# Last_project.net
KiCad netlist of a schematic drawn in Altium Designer
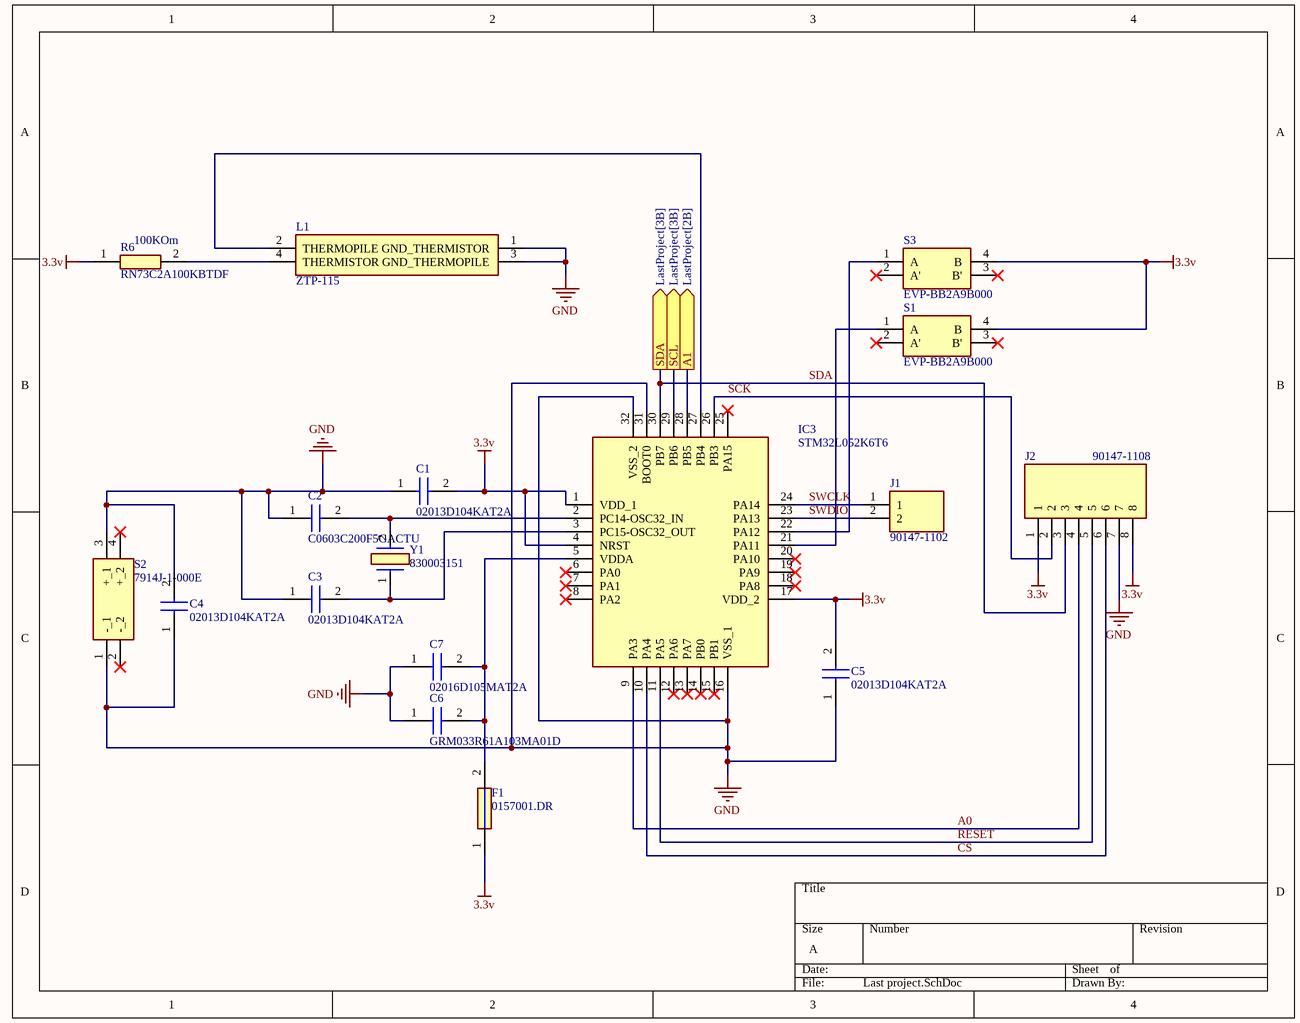
[diagram p0: Last project.SchDoc]

(export (version "E")
  (design (tool "Eeschema 10.0.6"))
  (components
    (comp (ref "C1")
      (value "02013D104KAT2A")
      (footprint "SamacSys:CAPC0603X33N")
      (description "Capacitor")
      (fields (field (name "MOUSER PART NUMBER") "581-02013D104KAT2A"))
      (libsource (lib "*") (part "02013D104KAT2A"))
    )
    (comp (ref "C2")
      (value "C0603C200F5GACTU")
      (footprint "SamacSys:CAPC1608X87N")
      (description "Capacitor")
      (fields (field (name "MOUSER PART NUMBER") "80-C0603C200F5GACTU"))
      (libsource (lib "*") (part "C0603C200F5GACTU"))
    )
    (comp (ref "C3")
      (value "02013D104KAT2A")
      (footprint "SamacSys:CAPC0603X33N")
      (description "Capacitor")
      (fields (field (name "MOUSER PART NUMBER") "581-02013D104KAT2A"))
      (libsource (lib "*") (part "02013D104KAT2A"))
    )
    (comp (ref "C4")
      (value "02013D104KAT2A")
      (footprint "SamacSys:CAPC0603X33N")
      (description "Capacitor")
      (fields (field (name "MOUSER PART NUMBER") "581-02013D104KAT2A"))
      (libsource (lib "*") (part "02013D104KAT2A"))
    )
    (comp (ref "C5")
      (value "02013D104KAT2A")
      (footprint "SamacSys:CAPC0603X33N")
      (description "Capacitor")
      (fields (field (name "MOUSER PART NUMBER") "581-02013D104KAT2A"))
      (libsource (lib "*") (part "02013D104KAT2A"))
    )
    (comp (ref "C6")
      (value "GRM033R61A103MA01D")
      (footprint "SamacSys:GRM033D70J224ME01D")
      (description "Capacitor")
      (fields (field (name "MOUSER PART NUMBER") "81-GRM033R61A103MA1D"))
      (libsource (lib "*") (part "GRM033R61A103MA01D"))
    )
    (comp (ref "C7")
      (value "02016D105MAT2A")
      (footprint "SamacSys:CAPC0603X33N")
      (description "Capacitor")
      (fields (field (name "MOUSER PART NUMBER") "581-02016D105MAT2A"))
      (libsource (lib "*") (part "02016D105MAT2A"))
    )
    (comp (ref "F1")
      (value "0157001.DR")
      (footprint "SamacSys:FUSC6537X403N")
      (description "Fuse")
      (fields (field (name "MOUSER PART NUMBER") "576-0157001.DR"))
      (libsource (lib "*") (part "0157001.DR"))
    )
    (comp (ref "IC3")
      (value "STM32L052K6T6")
      (footprint "SamacSys:QFP80P900X900X160-32N")
      (description "Integrated Circuit")
      (fields (field (name "MOUSER PART NUMBER") "511-STM32L052K6T6"))
      (libsource (lib "*") (part "STM32L052K6T6"))
    )
    (comp (ref "J1")
      (value "90147-1102")
      (footprint "SamacSys:RHDR2W70P0X254_1X2_493X244X870P")
      (description "Connector")
      (fields (field (name "MOUSER PART NUMBER") "538-90147-1102"))
      (libsource (lib "*") (part "90147-1102"))
    )
    (comp (ref "J2")
      (value "90147-1108")
      (footprint "SamacSys:RHDR8W70P0X254_1X8_2017X244X870P")
      (description "Connector")
      (fields (field (name "MOUSER PART NUMBER") "538-90147-1108"))
      (libsource (lib "*") (part "90147-1108"))
    )
    (comp (ref "L1")
      (value "ZTP-115")
      (footprint "SamacSys:ZTP115")
      (description "Inductor")
      (fields (field (name "MOUSER PART NUMBER") "527-ZTP-115-STD"))
      (libsource (lib "*") (part "ZTP-115"))
    )
    (comp (ref "R6")
      (value "RN73C2A100KBTDF")
      (footprint "SamacSys:RESC2012X65N")
      (description "Resistor")
      (fields (field (name "MOUSER PART NUMBER") "279-RN73CA-100K"))
      (libsource (lib "*") (part "RN73C2A100KBTDF"))
    )
    (comp (ref "S1")
      (value "EVP-BB2A9B000")
      (footprint "SamacSys:EVPBB2A9B000")
      (description "Switch")
      (fields (field (name "MOUSER PART NUMBER") "667-EVP-BB2A9B000"))
      (libsource (lib "*") (part "EVP-BB2A9B000"))
    )
    (comp (ref "S2")
      (value "7914J-1-000E")
      (footprint "SamacSys:7914J1000E")
      (description "Switch")
      (fields (field (name "MOUSER PART NUMBER") "652-7914J-1-000E"))
      (libsource (lib "*") (part "7914J-1-000E"))
    )
    (comp (ref "S3")
      (value "EVP-BB2A9B000")
      (footprint "SamacSys:EVPBB2A9B000")
      (description "Switch")
      (fields (field (name "MOUSER PART NUMBER") "667-EVP-BB2A9B000"))
      (libsource (lib "*") (part "EVP-BB2A9B000"))
    )
    (comp (ref "Y1")
      (value "830003151")
      (footprint "SamacSys:830003151")
      (description "Crystal or Oscillator")
      (fields (field (name "MOUSER PART NUMBER") "710-830003151"))
      (libsource (lib "*") (part "830003151"))
    )
  )
  (nets
    (net (code "1") (name "/A0") (class "Default")
      (node (ref "IC3") (pin "9") (pinfunction "PA3_9") (pintype "passive"))
      (node (ref "J2") (pin "4") (pinfunction "4_4") (pintype "passive"))
    )
    (net (code "2") (name "/A1") (class "Default")
      (node (ref "IC3") (pin "28") (pinfunction "PB5_28") (pintype "passive"))
    )
    (net (code "3") (name "/CS") (class "Default")
      (node (ref "IC3") (pin "10") (pinfunction "PA4_10") (pintype "passive"))
      (node (ref "J2") (pin "6") (pinfunction "6_6") (pintype "passive"))
    )
    (net (code "4") (name "/RESET") (class "Default")
      (node (ref "IC3") (pin "11") (pinfunction "PA5_11") (pintype "passive"))
      (node (ref "J2") (pin "5") (pinfunction "5_5") (pintype "passive"))
    )
    (net (code "5") (name "/SCK") (class "Default")
      (node (ref "IC3") (pin "26") (pinfunction "PB3_26") (pintype "passive"))
      (node (ref "J2") (pin "2") (pinfunction "2_2") (pintype "passive"))
    )
    (net (code "6") (name "/SCL") (class "Default")
      (node (ref "IC3") (pin "29") (pinfunction "PB6_29") (pintype "passive"))
    )
    (net (code "7") (name "/SDA") (class "Default")
      (node (ref "IC3") (pin "30") (pinfunction "PB7_30") (pintype "passive"))
      (node (ref "J2") (pin "3") (pinfunction "3_3") (pintype "passive"))
    )
    (net (code "8") (name "/SWCLK") (class "Default")
      (node (ref "IC3") (pin "24") (pinfunction "PA14_24") (pintype "passive"))
      (node (ref "J1") (pin "1") (pinfunction "1_1") (pintype "passive"))
    )
    (net (code "9") (name "/SWDIO") (class "Default")
      (node (ref "IC3") (pin "23") (pinfunction "PA13_23") (pintype "passive"))
      (node (ref "J1") (pin "2") (pinfunction "2_2") (pintype "passive"))
    )
    (net (code "10") (name "3.3v") (class "Default")
      (node (ref "C1") (pin "2") (pinfunction "2_2") (pintype "passive"))
      (node (ref "C5") (pin "2") (pinfunction "2_2") (pintype "passive"))
      (node (ref "F1") (pin "1") (pinfunction "1_1") (pintype "passive"))
      (node (ref "IC3") (pin "1") (pinfunction "VDD_1_1") (pintype "passive"))
      (node (ref "IC3") (pin "17") (pinfunction "VDD_2_17") (pintype "passive"))
      (node (ref "IC3") (pin "4") (pinfunction "NRST_4") (pintype "passive"))
      (node (ref "J2") (pin "1") (pinfunction "1_1") (pintype "passive"))
      (node (ref "J2") (pin "8") (pinfunction "8_8") (pintype "passive"))
      (node (ref "R6") (pin "1") (pinfunction "1_1") (pintype "passive"))
      (node (ref "S1") (pin "4") (pinfunction "B_4") (pintype "passive"))
      (node (ref "S3") (pin "4") (pinfunction "B_4") (pintype "passive"))
    )
    (net (code "11") (name "GND") (class "Default")
      (node (ref "C1") (pin "1") (pinfunction "1_1") (pintype "passive"))
      (node (ref "C2") (pin "1") (pinfunction "1_1") (pintype "passive"))
      (node (ref "C3") (pin "1") (pinfunction "1_1") (pintype "passive"))
      (node (ref "C4") (pin "1") (pinfunction "1_1") (pintype "passive"))
      (node (ref "C4") (pin "2") (pinfunction "2_2") (pintype "passive"))
      (node (ref "C5") (pin "1") (pinfunction "1_1") (pintype "passive"))
      (node (ref "C6") (pin "1") (pinfunction "1_1") (pintype "passive"))
      (node (ref "C7") (pin "1") (pinfunction "1_1") (pintype "passive"))
      (node (ref "IC3") (pin "16") (pinfunction "VSS_1_16") (pintype "passive"))
      (node (ref "IC3") (pin "31") (pinfunction "BOOT0_31") (pintype "passive"))
      (node (ref "IC3") (pin "32") (pinfunction "VSS_2_32") (pintype "passive"))
      (node (ref "J2") (pin "7") (pinfunction "7_7") (pintype "passive"))
      (node (ref "L1") (pin "1") (pinfunction "GND_THERMISTOR_1") (pintype "passive"))
      (node (ref "L1") (pin "3") (pinfunction "GND_THERMOPILE_3") (pintype "passive"))
      (node (ref "S2") (pin "1") (pinfunction "-_1_1") (pintype "passive"))
      (node (ref "S2") (pin "3") (pinfunction "+_1_3") (pintype "passive"))
    )
    (net (code "12") (name "Net-(IC3-PA11)") (class "Default")
      (node (ref "IC3") (pin "21") (pinfunction "PA11_21") (pintype "passive"))
      (node (ref "S1") (pin "1") (pinfunction "A_1") (pintype "passive"))
    )
    (net (code "13") (name "Net-(IC3-PA12)") (class "Default")
      (node (ref "IC3") (pin "22") (pinfunction "PA12_22") (pintype "passive"))
      (node (ref "S3") (pin "1") (pinfunction "A_1") (pintype "passive"))
    )
    (net (code "14") (name "Net-(IC3-PB4)") (class "Default")
      (node (ref "IC3") (pin "27") (pinfunction "PB4_27") (pintype "passive"))
      (node (ref "L1") (pin "2") (pinfunction "THERMOPILE_2") (pintype "passive"))
    )
    (net (code "15") (name "Net-(IC3-PC14-OSC32_IN)") (class "Default")
      (node (ref "C2") (pin "2") (pinfunction "2_2") (pintype "passive"))
      (node (ref "IC3") (pin "2") (pinfunction "PC14-OSC32_IN_2") (pintype "passive"))
      (node (ref "Y1") (pin "2") (pinfunction "2_2") (pintype "passive"))
    )
    (net (code "16") (name "Net-(IC3-PC15-OSC32_OUT)") (class "Default")
      (node (ref "C3") (pin "2") (pinfunction "2_2") (pintype "passive"))
      (node (ref "IC3") (pin "3") (pinfunction "PC15-OSC32_OUT_3") (pintype "passive"))
      (node (ref "Y1") (pin "1") (pinfunction "1_1") (pintype "passive"))
    )
    (net (code "17") (name "Net-(IC3-VDDA)") (class "Default")
      (node (ref "C6") (pin "2") (pinfunction "2_2") (pintype "passive"))
      (node (ref "C7") (pin "2") (pinfunction "2_2") (pintype "passive"))
      (node (ref "F1") (pin "2") (pinfunction "2_2") (pintype "passive"))
      (node (ref "IC3") (pin "5") (pinfunction "VDDA_5") (pintype "passive"))
    )
    (net (code "18") (name "Net-(L1-THERMISTOR)") (class "Default")
      (node (ref "L1") (pin "4") (pinfunction "THERMISTOR_4") (pintype "passive"))
      (node (ref "R6") (pin "2") (pinfunction "2_2") (pintype "passive"))
    )
    (net (code "19") (name "unconnected-(IC3-PA0-Pad6)") (class "Default")
      (node (ref "IC3") (pin "6") (pinfunction "PA0_6") (pintype "passive+no_connect"))
    )
    (net (code "20") (name "unconnected-(IC3-PA1-Pad7)") (class "Default")
      (node (ref "IC3") (pin "7") (pinfunction "PA1_7") (pintype "passive+no_connect"))
    )
    (net (code "21") (name "unconnected-(IC3-PA2-Pad8)") (class "Default")
      (node (ref "IC3") (pin "8") (pinfunction "PA2_8") (pintype "passive+no_connect"))
    )
    (net (code "22") (name "unconnected-(IC3-PA6-Pad12)") (class "Default")
      (node (ref "IC3") (pin "12") (pinfunction "PA6_12") (pintype "passive+no_connect"))
    )
    (net (code "23") (name "unconnected-(IC3-PA7-Pad13)") (class "Default")
      (node (ref "IC3") (pin "13") (pinfunction "PA7_13") (pintype "passive+no_connect"))
    )
    (net (code "24") (name "unconnected-(IC3-PA8-Pad18)") (class "Default")
      (node (ref "IC3") (pin "18") (pinfunction "PA8_18") (pintype "passive+no_connect"))
    )
    (net (code "25") (name "unconnected-(IC3-PA9-Pad19)") (class "Default")
      (node (ref "IC3") (pin "19") (pinfunction "PA9_19") (pintype "passive+no_connect"))
    )
    (net (code "26") (name "unconnected-(IC3-PA10-Pad20)") (class "Default")
      (node (ref "IC3") (pin "20") (pinfunction "PA10_20") (pintype "passive+no_connect"))
    )
    (net (code "27") (name "unconnected-(IC3-PA15-Pad25)") (class "Default")
      (node (ref "IC3") (pin "25") (pinfunction "PA15_25") (pintype "passive+no_connect"))
    )
    (net (code "28") (name "unconnected-(IC3-PB0-Pad14)") (class "Default")
      (node (ref "IC3") (pin "14") (pinfunction "PB0_14") (pintype "passive+no_connect"))
    )
    (net (code "29") (name "unconnected-(IC3-PB1-Pad15)") (class "Default")
      (node (ref "IC3") (pin "15") (pinfunction "PB1_15") (pintype "passive+no_connect"))
    )
    (net (code "30") (name "unconnected-(S1-A'-Pad2)") (class "Default")
      (node (ref "S1") (pin "2") (pinfunction "A'_2") (pintype "passive+no_connect"))
    )
    (net (code "31") (name "unconnected-(S1-B'-Pad3)") (class "Default")
      (node (ref "S1") (pin "3") (pinfunction "B'_3") (pintype "passive+no_connect"))
    )
    (net (code "32") (name "unconnected-(S2-+_2-Pad4)") (class "Default")
      (node (ref "S2") (pin "4") (pinfunction "+_2_4") (pintype "passive+no_connect"))
    )
    (net (code "33") (name "unconnected-(S2--_2-Pad2)") (class "Default")
      (node (ref "S2") (pin "2") (pinfunction "-_2_2") (pintype "passive+no_connect"))
    )
    (net (code "34") (name "unconnected-(S3-A'-Pad2)") (class "Default")
      (node (ref "S3") (pin "2") (pinfunction "A'_2") (pintype "passive+no_connect"))
    )
    (net (code "35") (name "unconnected-(S3-B'-Pad3)") (class "Default")
      (node (ref "S3") (pin "3") (pinfunction "B'_3") (pintype "passive+no_connect"))
    )
  )
)
